# DIB_555.net
KiCad netlist of a schematic drawn in Altium Designer
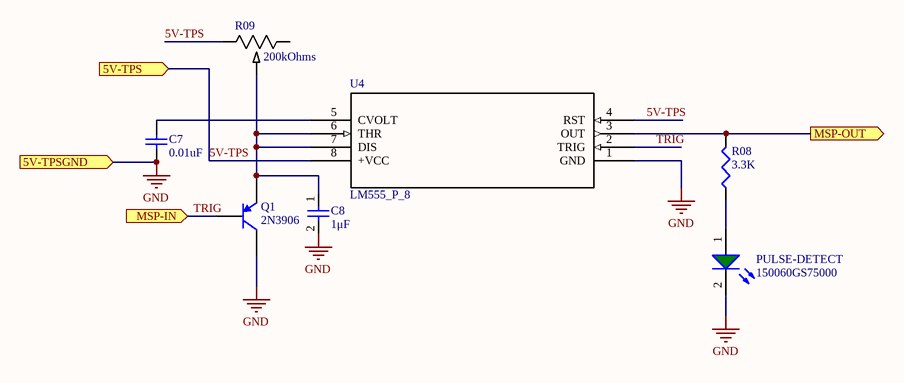
[diagram p0: DIB_555.SchDoc]

(export (version "E")
  (design (tool "Eeschema 10.0.6"))
  (components
    (comp (ref "C7")
      (value "0.01uF")
      (footprint "1608[0603]")
      (description "Capacitor (Semiconductor SIM Model)")
      (fields (field (name "PUBLISHER") "Altium Limited"))
      (libsource (lib "Miscellaneous Devices") (part "Cap Semi"))
    )
    (comp (ref "C8")
      (value "1μF")
      (footprint "WCAP-CSGP 0805, H=1.25mm")
      (description "CAP CER 1UF 50V 10% X5R 0805")
      (fields
        (field (name "MANUFACTURER") "TDK")
        (field (name "PARTNO") "CGA4J3X5R1H105K125AB")
        (field (name "CREATED BY") "Saurabh")
      )
      (libsource (lib "WCAP-CSGP_rev15b") (part "WCAP-CSGP 0805, 885012207026"))
    )
    (comp (ref "PULSE-DETECT")
      (value "150060GS75000")
      (footprint "LED_0603_Green")
      (description "SMD mono-color Chip LED, WL-SMCW, Green")
      (fields
        (field (name "MANUFACTURER") "W黵th Elektronik eiSos GmbH")
        (field (name "CREATED BY") "Christin Otto")
      )
      (libsource (lib "WL-SMCW_rev15b") (part "WL-SMCW 0603  150060GS75000"))
    )
    (comp (ref "Q1")
      (value "2N3906")
      (footprint "TO-92A")
      (description "PNP General Purpose Amplifier")
      (fields (field (name "PUBLISHER") "Altium Limited"))
      (libsource (lib "Miscellaneous Devices") (part "2N3906"))
    )
    (comp (ref "R08")
      (value "3.3K")
      (footprint "J1-0603")
      (description "Resistor")
      (fields (field (name "PUBLISHER") "Altium Limited"))
      (libsource (lib "Miscellaneous Devices") (part "Res3"))
    )
    (comp (ref "R09")
      (value "200kOhms")
      (footprint "POT_3006P")
      (description "Imported")
      (fields
        (field (name "MANUFACTURER_PART_NUMBER") "3006P-1-204LF")
        (field (name "TOLERANCE") "10%")
        (field (name "COPYRIGHT") "Copyright (C) 2015 Accelerated Designs. All rights reserved")
      )
      (libsource (lib "3006P-1-204") (part "3006P-1-204LF"))
    )
    (comp (ref "U4")
      (value "LM555_P_8")
      (footprint "M08A-M")
      (description "Imported")
      (fields (field (name "MANUFACTURER_PART_NUMBER") "lm555cnnopb"))
      (libsource (lib "2016-04-05_16-30-27") (part "LM555_P_8"))
    )
  )
  (nets
    (net (code "1") (name "/5V-TPS") (class "Default")
      (node (ref "R09") (pin "3") (pinfunction "3_3") (pintype "passive"))
      (node (ref "U4") (pin "4") (pinfunction "RST_4") (pintype "input"))
      (node (ref "U4") (pin "8") (pinfunction "+VCC_8") (pintype "power_in"))
    )
    (net (code "2") (name "/MSP-OUT") (class "Default")
      (node (ref "R08") (pin "2") (pinfunction "2_2") (pintype "passive"))
      (node (ref "U4") (pin "3") (pinfunction "OUT_3") (pintype "output"))
    )
    (net (code "3") (name "/TRIG") (class "Default")
      (node (ref "Q1") (pin "2") (pinfunction "B_2") (pintype "passive"))
      (node (ref "U4") (pin "2") (pinfunction "TRIG_2") (pintype "input"))
    )
    (net (code "4") (name "GND") (class "Default")
      (node (ref "C7") (pin "1") (pinfunction "1_1") (pintype "passive"))
      (node (ref "C8") (pin "2") (pinfunction "2_2") (pintype "passive"))
      (node (ref "PULSE-DETECT") (pin "2") (pinfunction "C_2") (pintype "passive"))
      (node (ref "Q1") (pin "3") (pinfunction "C_3") (pintype "passive"))
      (node (ref "U4") (pin "1") (pinfunction "GND_1") (pintype "power_in"))
    )
    (net (code "5") (name "Net-(PULSE-DETECT-A)") (class "Default")
      (node (ref "PULSE-DETECT") (pin "1") (pinfunction "A_1") (pintype "passive"))
      (node (ref "R08") (pin "1") (pinfunction "1_1") (pintype "passive"))
    )
    (net (code "6") (name "Net-(Q1-E)") (class "Default")
      (node (ref "C8") (pin "1") (pinfunction "1_1") (pintype "passive"))
      (node (ref "Q1") (pin "1") (pinfunction "E_1") (pintype "passive"))
      (node (ref "R09") (pin "2") (pinfunction "2_2") (pintype "passive"))
      (node (ref "U4") (pin "6") (pinfunction "THR_6") (pintype "input"))
      (node (ref "U4") (pin "7") (pinfunction "DIS_7") (pintype "passive"))
    )
    (net (code "7") (name "Net-(U4-CVOLT)") (class "Default")
      (node (ref "C7") (pin "2") (pinfunction "2_2") (pintype "passive"))
      (node (ref "U4") (pin "5") (pinfunction "CVOLT_5") (pintype "passive"))
    )
    (net (code "8") (name "unconnected-(R09-Pad1)") (class "Default")
      (node (ref "R09") (pin "1") (pinfunction "1_1") (pintype "passive"))
    )
  )
)
